# C-08_SODIMM.net
KiCad netlist of a schematic drawn in Altium Designer
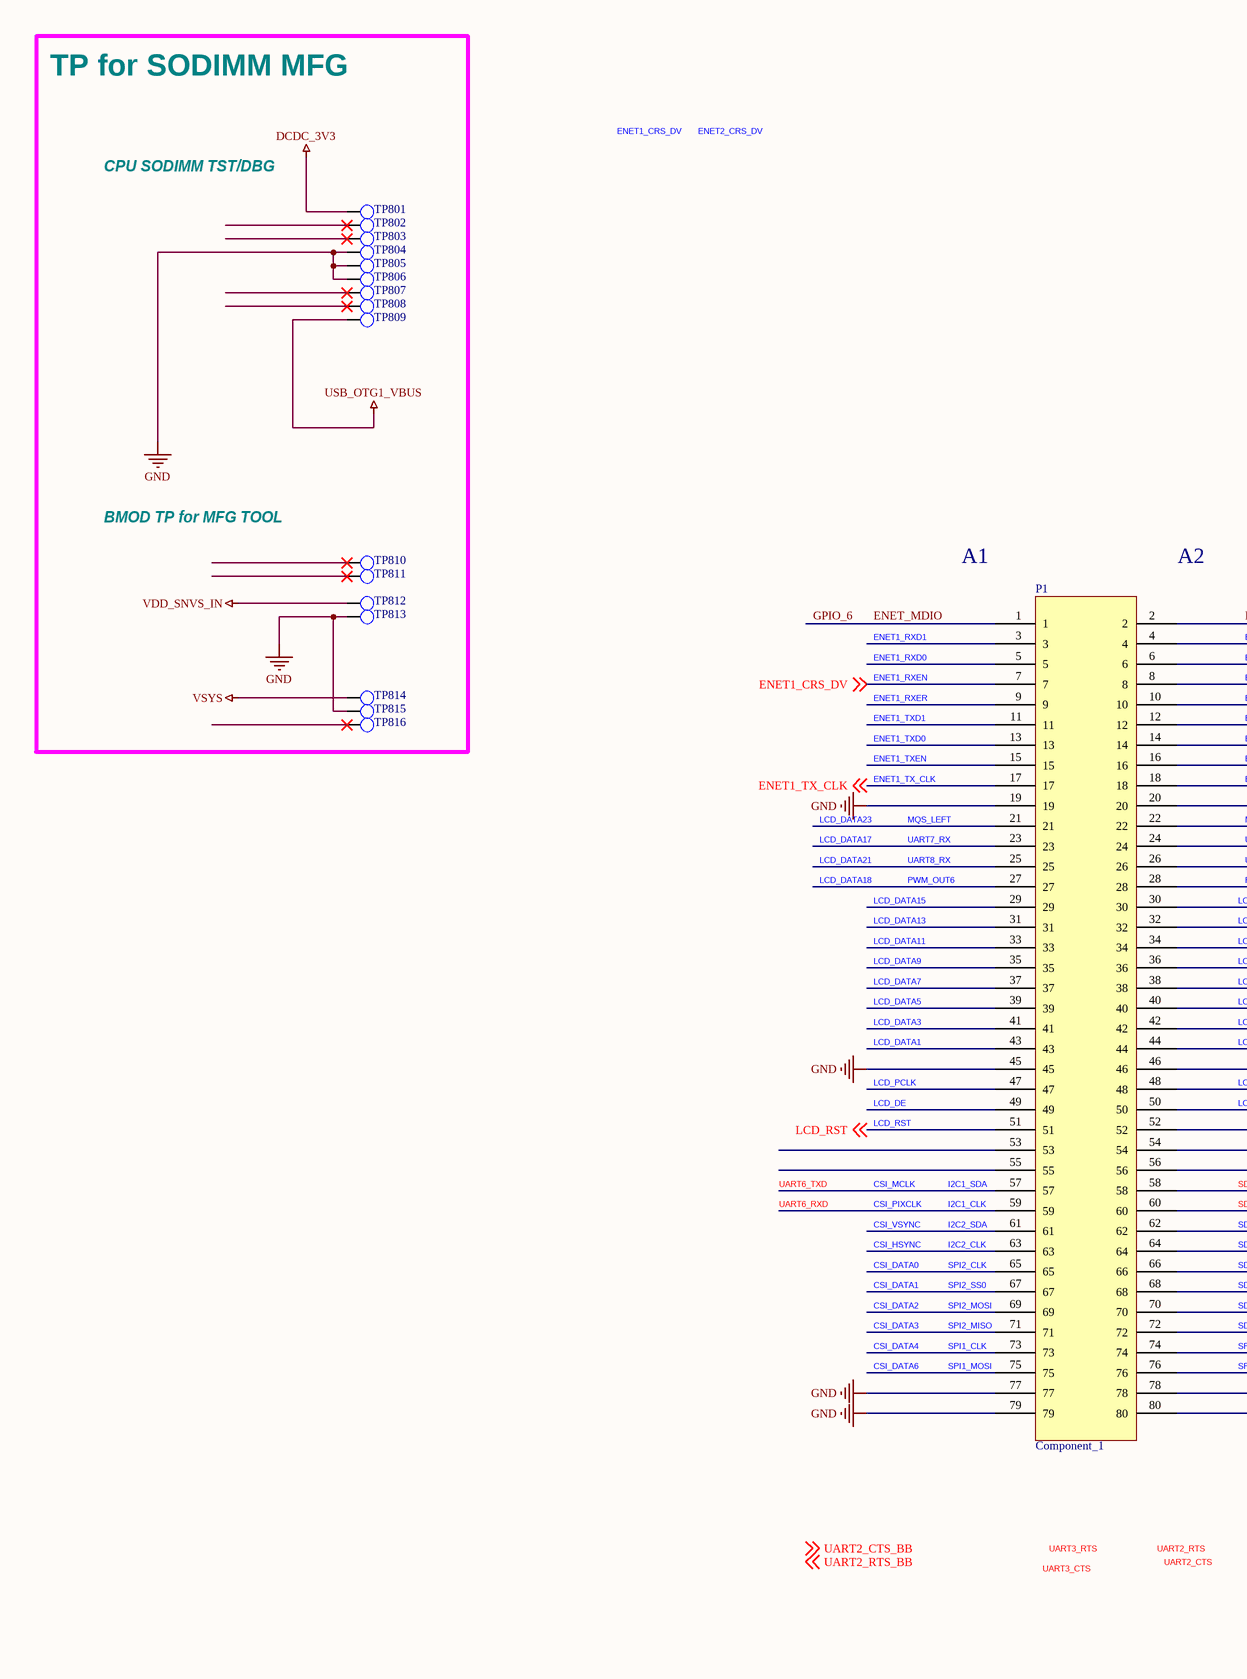
[diagram p0: C-08 SODIMM.SchDoc, left]
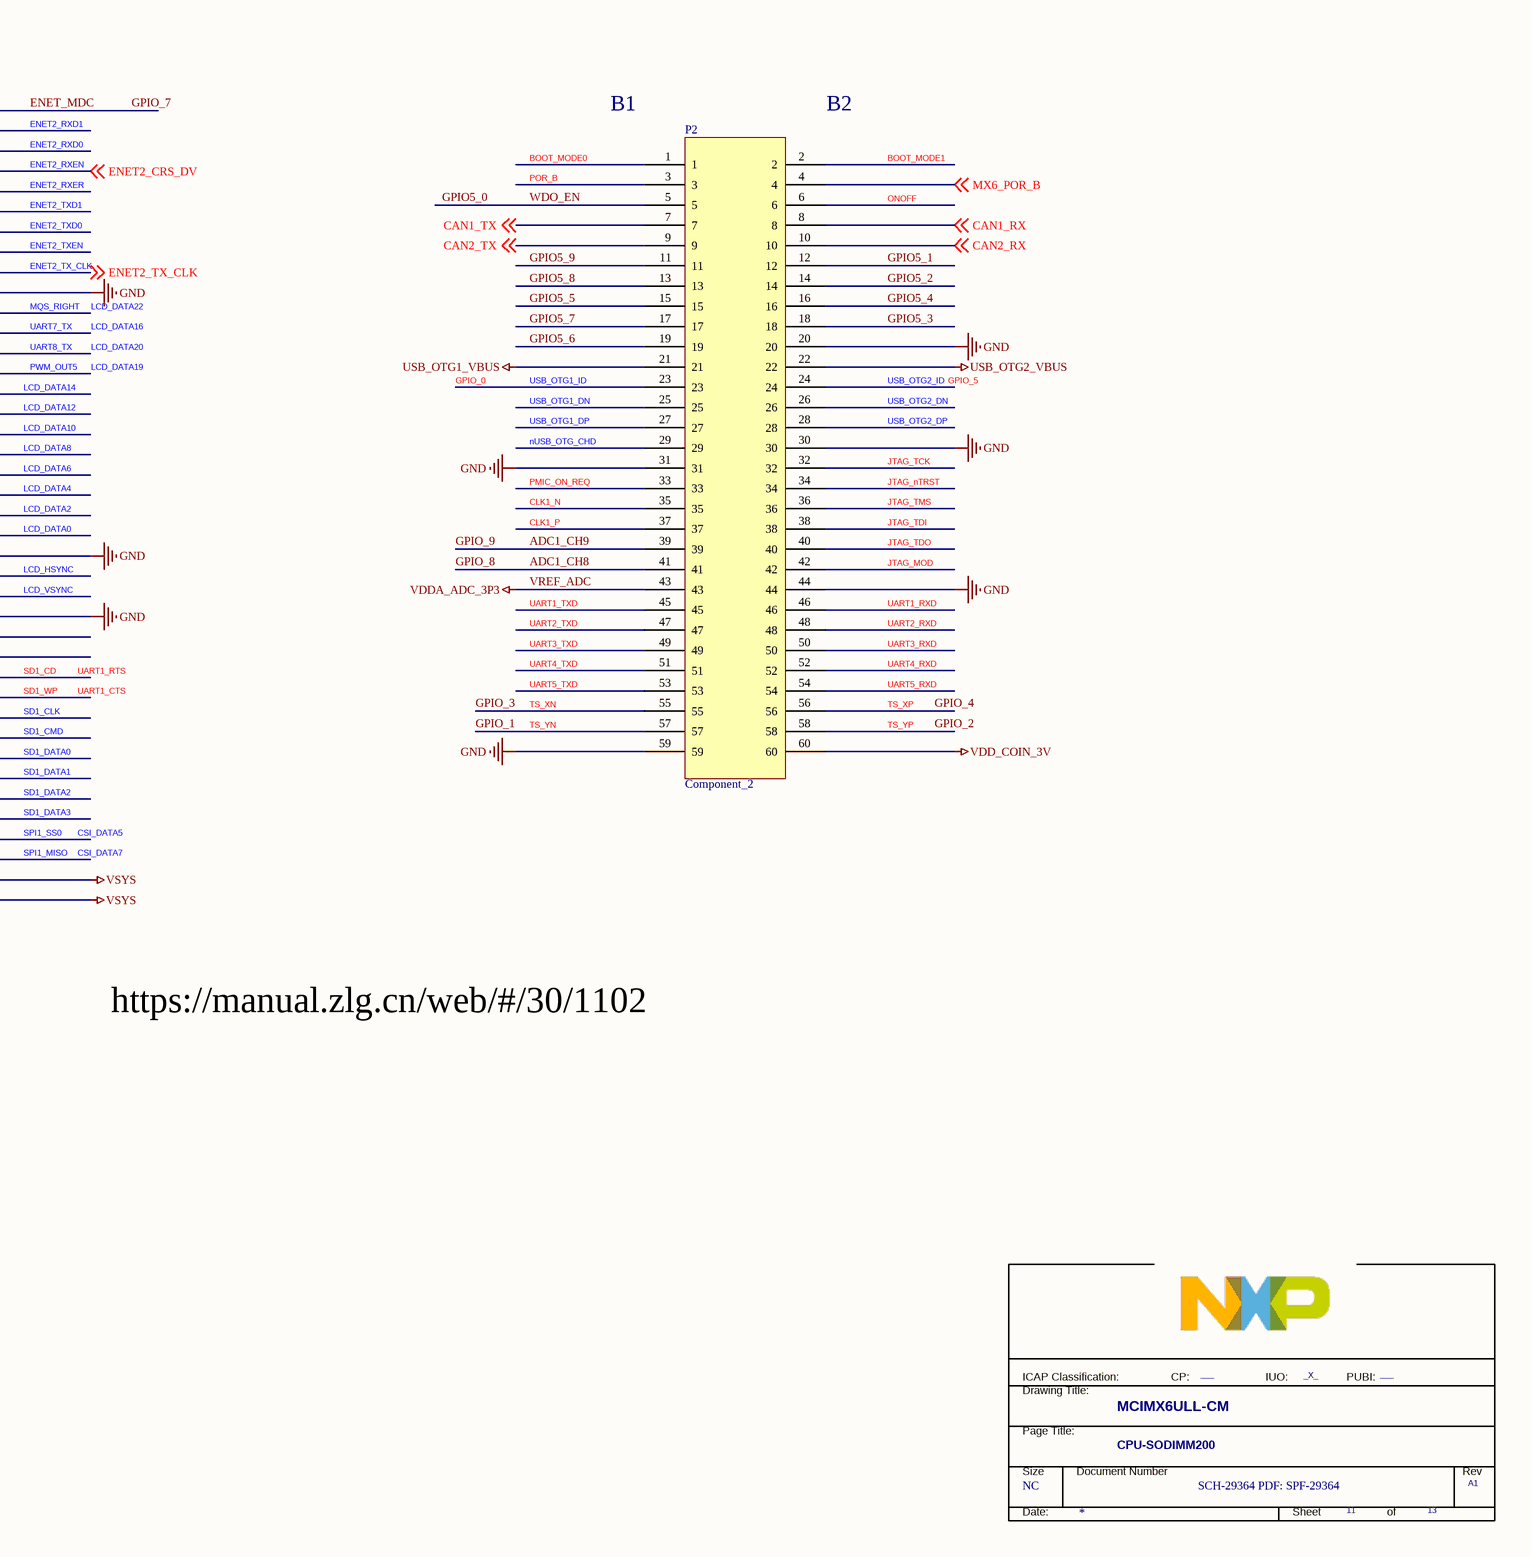
[diagram p1: C-08 SODIMM.SchDoc, right]

(export (version "E")
  (design (tool "Eeschema 10.0.6"))
  (components
    (comp (ref "*")
      (value "TitleBlock_FS")
      (fields
        (field (name "PAGETITLE") "CPU-SODIMM200")
        (field (name "PAGE COUNT") "13")
        (field (name "PAGE NUMBER") "11")
        (field (name "PAGE SIZE") "NC")
        (field (name "TITLE") "MCIMX6ULL-CM")
        (field (name "REVCODE") "A1")
        (field (name "DOC") "SCH-29364 PDF: SPF-29364")
        (field (name "FCP") "___")
        (field (name "PUBI") "___")
        (field (name "FIUO") "_X_")
      )
      (libsource (lib "*") (part "TitleBlock_FS"))
    )
    (comp (ref "P1")
      (value "Component_1")
      (footprint "CONN-SMD_80P-P0.50_HRS_DF12NB3.0-80DP-0.5V")
      (libsource (lib "Schlib1") (part "Component_1"))
    )
    (comp (ref "P2")
      (value "Component_2")
      (footprint "CONN-SMD_60P-P0.50_HRS_DF12NB3.0-60DS-0.5V-51")
      (libsource (lib "Schlib1") (part "Component_2"))
    )
    (comp (ref "TP801")
      (value "TP_35MIL")
      (footprint "testpoint_35mil")
      (description "TEST POINT PAD .035 SMT, no part to order")
      (libsource (lib "*") (part "T POINT R"))
    )
    (comp (ref "TP802")
      (value "TP_35MIL")
      (footprint "testpoint_35mil")
      (description "TEST POINT PAD .035 SMT, no part to order")
      (libsource (lib "*") (part "T POINT R"))
    )
    (comp (ref "TP803")
      (value "TP_35MIL")
      (footprint "testpoint_35mil")
      (description "TEST POINT PAD .035 SMT, no part to order")
      (libsource (lib "*") (part "T POINT R"))
    )
    (comp (ref "TP804")
      (value "TP_35MIL")
      (footprint "testpoint_35mil")
      (description "TEST POINT PAD .035 SMT, no part to order")
      (libsource (lib "*") (part "T POINT R"))
    )
    (comp (ref "TP805")
      (value "TP_35MIL")
      (footprint "testpoint_35mil")
      (description "TEST POINT PAD .035 SMT, no part to order")
      (libsource (lib "*") (part "T POINT R"))
    )
    (comp (ref "TP806")
      (value "TP_35MIL")
      (footprint "testpoint_35mil")
      (description "TEST POINT PAD .035 SMT, no part to order")
      (libsource (lib "*") (part "T POINT R"))
    )
    (comp (ref "TP807")
      (value "TP_35MIL")
      (footprint "testpoint_35mil")
      (description "TEST POINT PAD .035 SMT, no part to order")
      (libsource (lib "*") (part "T POINT R"))
    )
    (comp (ref "TP808")
      (value "TP_35MIL")
      (footprint "testpoint_35mil")
      (description "TEST POINT PAD .035 SMT, no part to order")
      (libsource (lib "*") (part "T POINT R"))
    )
    (comp (ref "TP809")
      (value "TP_35MIL")
      (footprint "testpoint_35mil")
      (description "TEST POINT PAD .035 SMT, no part to order")
      (libsource (lib "*") (part "T POINT R"))
    )
    (comp (ref "TP810")
      (value "TP_35MIL")
      (footprint "testpoint_35mil")
      (description "TEST POINT PAD .035 SMT, no part to order")
      (libsource (lib "*") (part "T POINT R"))
    )
    (comp (ref "TP811")
      (value "TP_35MIL")
      (footprint "testpoint_35mil")
      (description "TEST POINT PAD .035 SMT, no part to order")
      (libsource (lib "*") (part "T POINT R"))
    )
    (comp (ref "TP812")
      (value "TP_35MIL")
      (footprint "TPAD_015")
      (description "TEST POINT PAD .035 SMT, no part to order")
      (libsource (lib "*") (part "T POINT R"))
    )
    (comp (ref "TP813")
      (value "TP_35MIL")
      (footprint "testpoint_35mil")
      (description "TEST POINT PAD .035 SMT, no part to order")
      (libsource (lib "*") (part "T POINT R"))
    )
    (comp (ref "TP814")
      (value "TP_35MIL")
      (footprint "testpoint_35mil")
      (description "TEST POINT PAD .035 SMT, no part to order")
      (libsource (lib "*") (part "T POINT R"))
    )
    (comp (ref "TP815")
      (value "TP_35MIL")
      (footprint "testpoint_35mil")
      (description "TEST POINT PAD .035 SMT, no part to order")
      (libsource (lib "*") (part "T POINT R"))
    )
    (comp (ref "TP816")
      (value "TP_35MIL")
      (footprint "testpoint_35mil")
      (description "TEST POINT PAD .035 SMT, no part to order")
      (libsource (lib "*") (part "T POINT R"))
    )
  )
  (nets
    (net (code "1") (name "/ADC1_CH8") (class "Default")
      (node (ref "P2") (pin "41") (pinfunction "41_41") (pintype "passive"))
    )
    (net (code "2") (name "/ADC1_CH9") (class "Default")
      (node (ref "P2") (pin "39") (pinfunction "39_39") (pintype "passive"))
    )
    (net (code "3") (name "/BOOT_MODE0") (class "Default")
      (node (ref "P2") (pin "1") (pinfunction "1_1") (pintype "passive"))
    )
    (net (code "4") (name "/BOOT_MODE1") (class "Default")
      (node (ref "P2") (pin "2") (pinfunction "2_2") (pintype "passive"))
    )
    (net (code "5") (name "/CLK1_N") (class "Default")
      (node (ref "P2") (pin "35") (pinfunction "35_35") (pintype "passive"))
    )
    (net (code "6") (name "/CLK1_P") (class "Default")
      (node (ref "P2") (pin "37") (pinfunction "37_37") (pintype "passive"))
    )
    (net (code "7") (name "/CSI_DATA0") (class "Default")
      (node (ref "P1") (pin "65") (pinfunction "65_65") (pintype "passive"))
    )
    (net (code "8") (name "/CSI_DATA1") (class "Default")
      (node (ref "P1") (pin "67") (pinfunction "67_67") (pintype "passive"))
    )
    (net (code "9") (name "/CSI_DATA2") (class "Default")
      (node (ref "P1") (pin "69") (pinfunction "69_69") (pintype "passive"))
    )
    (net (code "10") (name "/CSI_DATA3") (class "Default")
      (node (ref "P1") (pin "71") (pinfunction "71_71") (pintype "passive"))
    )
    (net (code "11") (name "/CSI_DATA4") (class "Default")
      (node (ref "P1") (pin "73") (pinfunction "73_73") (pintype "passive"))
    )
    (net (code "12") (name "/CSI_DATA5") (class "Default")
      (node (ref "P1") (pin "74") (pinfunction "74_74") (pintype "passive"))
    )
    (net (code "13") (name "/CSI_DATA6") (class "Default")
      (node (ref "P1") (pin "75") (pinfunction "75_75") (pintype "passive"))
    )
    (net (code "14") (name "/CSI_DATA7") (class "Default")
      (node (ref "P1") (pin "76") (pinfunction "76_76") (pintype "passive"))
    )
    (net (code "15") (name "/CSI_HSYNC") (class "Default")
      (node (ref "P1") (pin "63") (pinfunction "63_63") (pintype "passive"))
    )
    (net (code "16") (name "/CSI_MCLK") (class "Default")
      (node (ref "P1") (pin "57") (pinfunction "57_57") (pintype "passive"))
    )
    (net (code "17") (name "/CSI_PIXCLK") (class "Default")
      (node (ref "P1") (pin "59") (pinfunction "59_59") (pintype "passive"))
    )
    (net (code "18") (name "/CSI_VSYNC") (class "Default")
      (node (ref "P1") (pin "61") (pinfunction "61_61") (pintype "passive"))
    )
    (net (code "19") (name "/ENET1_RXD0") (class "Default")
      (node (ref "P1") (pin "5") (pinfunction "5_5") (pintype "passive"))
    )
    (net (code "20") (name "/ENET1_RXD1") (class "Default")
      (node (ref "P1") (pin "3") (pinfunction "3_3") (pintype "passive"))
    )
    (net (code "21") (name "/ENET1_RXER") (class "Default")
      (node (ref "P1") (pin "9") (pinfunction "9_9") (pintype "passive"))
    )
    (net (code "22") (name "/ENET1_TXD0") (class "Default")
      (node (ref "P1") (pin "13") (pinfunction "13_13") (pintype "passive"))
    )
    (net (code "23") (name "/ENET1_TXD1") (class "Default")
      (node (ref "P1") (pin "11") (pinfunction "11_11") (pintype "passive"))
    )
    (net (code "24") (name "/ENET1_TXEN") (class "Default")
      (node (ref "P1") (pin "15") (pinfunction "15_15") (pintype "passive"))
    )
    (net (code "25") (name "/ENET2_RXD0") (class "Default")
      (node (ref "P1") (pin "6") (pinfunction "6_6") (pintype "passive"))
    )
    (net (code "26") (name "/ENET2_RXD1") (class "Default")
      (node (ref "P1") (pin "4") (pinfunction "4_4") (pintype "passive"))
    )
    (net (code "27") (name "/ENET2_RXER") (class "Default")
      (node (ref "P1") (pin "10") (pinfunction "10_10") (pintype "passive"))
    )
    (net (code "28") (name "/ENET2_TXD0") (class "Default")
      (node (ref "P1") (pin "14") (pinfunction "14_14") (pintype "passive"))
    )
    (net (code "29") (name "/ENET2_TXD1") (class "Default")
      (node (ref "P1") (pin "12") (pinfunction "12_12") (pintype "passive"))
    )
    (net (code "30") (name "/ENET2_TXEN") (class "Default")
      (node (ref "P1") (pin "16") (pinfunction "16_16") (pintype "passive"))
    )
    (net (code "31") (name "/ENET_MDC") (class "Default")
      (node (ref "P1") (pin "2") (pinfunction "2_2") (pintype "passive"))
    )
    (net (code "32") (name "/ENET_MDIO") (class "Default")
      (node (ref "P1") (pin "1") (pinfunction "1_1") (pintype "passive"))
    )
    (net (code "33") (name "/GPIO5_0") (class "Default")
      (node (ref "P2") (pin "5") (pinfunction "5_5") (pintype "passive"))
    )
    (net (code "34") (name "/GPIO5_1") (class "Default")
      (node (ref "P2") (pin "12") (pinfunction "12_12") (pintype "passive"))
    )
    (net (code "35") (name "/GPIO5_2") (class "Default")
      (node (ref "P2") (pin "14") (pinfunction "14_14") (pintype "passive"))
    )
    (net (code "36") (name "/GPIO5_3") (class "Default")
      (node (ref "P2") (pin "18") (pinfunction "18_18") (pintype "passive"))
    )
    (net (code "37") (name "/GPIO5_4") (class "Default")
      (node (ref "P2") (pin "16") (pinfunction "16_16") (pintype "passive"))
    )
    (net (code "38") (name "/GPIO5_5") (class "Default")
      (node (ref "P2") (pin "15") (pinfunction "15_15") (pintype "passive"))
    )
    (net (code "39") (name "/GPIO5_6") (class "Default")
      (node (ref "P2") (pin "19") (pinfunction "19_19") (pintype "passive"))
    )
    (net (code "40") (name "/GPIO5_7") (class "Default")
      (node (ref "P2") (pin "17") (pinfunction "17_17") (pintype "passive"))
    )
    (net (code "41") (name "/GPIO5_8") (class "Default")
      (node (ref "P2") (pin "13") (pinfunction "13_13") (pintype "passive"))
    )
    (net (code "42") (name "/GPIO5_9") (class "Default")
      (node (ref "P2") (pin "11") (pinfunction "11_11") (pintype "passive"))
    )
    (net (code "43") (name "/GPIO_0") (class "Default")
      (node (ref "P2") (pin "23") (pinfunction "23_23") (pintype "passive"))
    )
    (net (code "44") (name "/GPIO_1") (class "Default")
      (node (ref "P2") (pin "57") (pinfunction "57_57") (pintype "passive"))
    )
    (net (code "45") (name "/GPIO_2") (class "Default")
      (node (ref "P2") (pin "58") (pinfunction "58_58") (pintype "passive"))
    )
    (net (code "46") (name "/GPIO_3") (class "Default")
      (node (ref "P2") (pin "55") (pinfunction "55_55") (pintype "passive"))
    )
    (net (code "47") (name "/GPIO_4") (class "Default")
      (node (ref "P2") (pin "56") (pinfunction "56_56") (pintype "passive"))
    )
    (net (code "48") (name "/GPIO_5") (class "Default")
      (node (ref "P2") (pin "24") (pinfunction "24_24") (pintype "passive"))
    )
    (net (code "49") (name "/JTAG_MOD") (class "Default")
      (node (ref "P2") (pin "42") (pinfunction "42_42") (pintype "passive"))
    )
    (net (code "50") (name "/JTAG_TCK") (class "Default")
      (node (ref "P2") (pin "32") (pinfunction "32_32") (pintype "passive"))
    )
    (net (code "51") (name "/JTAG_TDI") (class "Default")
      (node (ref "P2") (pin "38") (pinfunction "38_38") (pintype "passive"))
    )
    (net (code "52") (name "/JTAG_TDO") (class "Default")
      (node (ref "P2") (pin "40") (pinfunction "40_40") (pintype "passive"))
    )
    (net (code "53") (name "/JTAG_TMS") (class "Default")
      (node (ref "P2") (pin "36") (pinfunction "36_36") (pintype "passive"))
    )
    (net (code "54") (name "/JTAG_nTRST") (class "Default")
      (node (ref "P2") (pin "34") (pinfunction "34_34") (pintype "passive"))
    )
    (net (code "55") (name "/LCD_DATA0") (class "Default")
      (node (ref "P1") (pin "44") (pinfunction "44_44") (pintype "passive"))
    )
    (net (code "56") (name "/LCD_DATA1") (class "Default")
      (node (ref "P1") (pin "43") (pinfunction "43_43") (pintype "passive"))
    )
    (net (code "57") (name "/LCD_DATA2") (class "Default")
      (node (ref "P1") (pin "42") (pinfunction "42_42") (pintype "passive"))
    )
    (net (code "58") (name "/LCD_DATA3") (class "Default")
      (node (ref "P1") (pin "41") (pinfunction "41_41") (pintype "passive"))
    )
    (net (code "59") (name "/LCD_DATA4") (class "Default")
      (node (ref "P1") (pin "40") (pinfunction "40_40") (pintype "passive"))
    )
    (net (code "60") (name "/LCD_DATA5") (class "Default")
      (node (ref "P1") (pin "39") (pinfunction "39_39") (pintype "passive"))
    )
    (net (code "61") (name "/LCD_DATA6") (class "Default")
      (node (ref "P1") (pin "38") (pinfunction "38_38") (pintype "passive"))
    )
    (net (code "62") (name "/LCD_DATA7") (class "Default")
      (node (ref "P1") (pin "37") (pinfunction "37_37") (pintype "passive"))
    )
    (net (code "63") (name "/LCD_DATA8") (class "Default")
      (node (ref "P1") (pin "36") (pinfunction "36_36") (pintype "passive"))
    )
    (net (code "64") (name "/LCD_DATA9") (class "Default")
      (node (ref "P1") (pin "35") (pinfunction "35_35") (pintype "passive"))
    )
    (net (code "65") (name "/LCD_DATA10") (class "Default")
      (node (ref "P1") (pin "34") (pinfunction "34_34") (pintype "passive"))
    )
    (net (code "66") (name "/LCD_DATA11") (class "Default")
      (node (ref "P1") (pin "33") (pinfunction "33_33") (pintype "passive"))
    )
    (net (code "67") (name "/LCD_DATA12") (class "Default")
      (node (ref "P1") (pin "32") (pinfunction "32_32") (pintype "passive"))
    )
    (net (code "68") (name "/LCD_DATA13") (class "Default")
      (node (ref "P1") (pin "31") (pinfunction "31_31") (pintype "passive"))
    )
    (net (code "69") (name "/LCD_DATA14") (class "Default")
      (node (ref "P1") (pin "30") (pinfunction "30_30") (pintype "passive"))
    )
    (net (code "70") (name "/LCD_DATA15") (class "Default")
      (node (ref "P1") (pin "29") (pinfunction "29_29") (pintype "passive"))
    )
    (net (code "71") (name "/LCD_DATA16") (class "Default")
      (node (ref "P1") (pin "24") (pinfunction "24_24") (pintype "passive"))
    )
    (net (code "72") (name "/LCD_DATA17") (class "Default")
      (node (ref "P1") (pin "23") (pinfunction "23_23") (pintype "passive"))
    )
    (net (code "73") (name "/LCD_DATA18") (class "Default")
      (node (ref "P1") (pin "27") (pinfunction "27_27") (pintype "passive"))
    )
    (net (code "74") (name "/LCD_DATA19") (class "Default")
      (node (ref "P1") (pin "28") (pinfunction "28_28") (pintype "passive"))
    )
    (net (code "75") (name "/LCD_DATA20") (class "Default")
      (node (ref "P1") (pin "26") (pinfunction "26_26") (pintype "passive"))
    )
    (net (code "76") (name "/LCD_DATA21") (class "Default")
      (node (ref "P1") (pin "25") (pinfunction "25_25") (pintype "passive"))
    )
    (net (code "77") (name "/LCD_DATA22") (class "Default")
      (node (ref "P1") (pin "22") (pinfunction "22_22") (pintype "passive"))
    )
    (net (code "78") (name "/LCD_DATA23") (class "Default")
      (node (ref "P1") (pin "21") (pinfunction "21_21") (pintype "passive"))
    )
    (net (code "79") (name "/LCD_DE") (class "Default")
      (node (ref "P1") (pin "49") (pinfunction "49_49") (pintype "passive"))
    )
    (net (code "80") (name "/LCD_HSYNC") (class "Default")
      (node (ref "P1") (pin "48") (pinfunction "48_48") (pintype "passive"))
    )
    (net (code "81") (name "/LCD_PCLK") (class "Default")
      (node (ref "P1") (pin "47") (pinfunction "47_47") (pintype "passive"))
    )
    (net (code "82") (name "/LCD_VSYNC") (class "Default")
      (node (ref "P1") (pin "50") (pinfunction "50_50") (pintype "passive"))
    )
    (net (code "83") (name "/ONOFF") (class "Default")
      (node (ref "P2") (pin "6") (pinfunction "6_6") (pintype "passive"))
    )
    (net (code "84") (name "/PMIC_ON_REQ") (class "Default")
      (node (ref "P2") (pin "33") (pinfunction "33_33") (pintype "passive"))
    )
    (net (code "85") (name "/POR_B") (class "Default")
      (node (ref "P2") (pin "3") (pinfunction "3_3") (pintype "passive"))
    )
    (net (code "86") (name "/SD1_CD") (class "Default")
      (node (ref "P1") (pin "58") (pinfunction "58_58") (pintype "passive"))
    )
    (net (code "87") (name "/SD1_CLK") (class "Default")
      (node (ref "P1") (pin "62") (pinfunction "62_62") (pintype "passive"))
    )
    (net (code "88") (name "/SD1_CMD") (class "Default")
      (node (ref "P1") (pin "64") (pinfunction "64_64") (pintype "passive"))
    )
    (net (code "89") (name "/SD1_DATA0") (class "Default")
      (node (ref "P1") (pin "66") (pinfunction "66_66") (pintype "passive"))
    )
    (net (code "90") (name "/SD1_DATA1") (class "Default")
      (node (ref "P1") (pin "68") (pinfunction "68_68") (pintype "passive"))
    )
    (net (code "91") (name "/SD1_DATA2") (class "Default")
      (node (ref "P1") (pin "70") (pinfunction "70_70") (pintype "passive"))
    )
    (net (code "92") (name "/SD1_DATA3") (class "Default")
      (node (ref "P1") (pin "72") (pinfunction "72_72") (pintype "passive"))
    )
    (net (code "93") (name "/SD1_WP") (class "Default")
      (node (ref "P1") (pin "60") (pinfunction "60_60") (pintype "passive"))
    )
    (net (code "94") (name "/UART1_RXD") (class "Default")
      (node (ref "P2") (pin "46") (pinfunction "46_46") (pintype "passive"))
    )
    (net (code "95") (name "/UART1_TXD") (class "Default")
      (node (ref "P2") (pin "45") (pinfunction "45_45") (pintype "passive"))
    )
    (net (code "98") (name "/UART2_RXD") (class "Default")
      (node (ref "P2") (pin "48") (pinfunction "48_48") (pintype "passive"))
    )
    (net (code "99") (name "/UART2_TXD") (class "Default")
      (node (ref "P2") (pin "47") (pinfunction "47_47") (pintype "passive"))
    )
    (net (code "102") (name "/UART3_RXD") (class "Default")
      (node (ref "P2") (pin "50") (pinfunction "50_50") (pintype "passive"))
    )
    (net (code "103") (name "/UART3_TXD") (class "Default")
      (node (ref "P2") (pin "49") (pinfunction "49_49") (pintype "passive"))
    )
    (net (code "104") (name "/UART4_RXD") (class "Default")
      (node (ref "P2") (pin "52") (pinfunction "52_52") (pintype "passive"))
    )
    (net (code "105") (name "/UART4_TXD") (class "Default")
      (node (ref "P2") (pin "51") (pinfunction "51_51") (pintype "passive"))
    )
    (net (code "106") (name "/UART5_RXD") (class "Default")
      (node (ref "P2") (pin "54") (pinfunction "54_54") (pintype "passive"))
    )
    (net (code "107") (name "/UART5_TXD") (class "Default")
      (node (ref "P2") (pin "53") (pinfunction "53_53") (pintype "passive"))
    )
    (net (code "108") (name "/USB_OTG1_DN") (class "Default")
      (node (ref "P2") (pin "25") (pinfunction "25_25") (pintype "passive"))
    )
    (net (code "109") (name "/USB_OTG1_DP") (class "Default")
      (node (ref "P2") (pin "27") (pinfunction "27_27") (pintype "passive"))
    )
    (net (code "110") (name "/USB_OTG2_DN") (class "Default")
      (node (ref "P2") (pin "26") (pinfunction "26_26") (pintype "passive"))
    )
    (net (code "111") (name "/USB_OTG2_DP") (class "Default")
      (node (ref "P2") (pin "28") (pinfunction "28_28") (pintype "passive"))
    )
    (net (code "112") (name "/nUSB_OTG_CHD") (class "Default")
      (node (ref "P2") (pin "29") (pinfunction "29_29") (pintype "passive"))
    )
    (net (code "113") (name "CAN1_RX") (class "Default")
      (node (ref "P2") (pin "8") (pinfunction "8_8") (pintype "passive"))
    )
    (net (code "114") (name "CAN1_TX") (class "Default")
      (node (ref "P2") (pin "7") (pinfunction "7_7") (pintype "passive"))
    )
    (net (code "115") (name "CAN2_RX") (class "Default")
      (node (ref "P2") (pin "10") (pinfunction "10_10") (pintype "passive"))
    )
    (net (code "116") (name "CAN2_TX") (class "Default")
      (node (ref "P2") (pin "9") (pinfunction "9_9") (pintype "passive"))
    )
    (net (code "117") (name "DCDC_3V3") (class "Default")
      (node (ref "TP801") (pin "1") (pinfunction "TP_1") (pintype "passive"))
    )
    (net (code "118") (name "ENET1_CRS_DV") (class "Default")
      (node (ref "P1") (pin "7") (pinfunction "7_7") (pintype "passive"))
    )
    (net (code "119") (name "ENET1_TX_CLK") (class "Default")
      (node (ref "P1") (pin "17") (pinfunction "17_17") (pintype "passive"))
    )
    (net (code "120") (name "ENET2_CRS_DV") (class "Default")
      (node (ref "P1") (pin "8") (pinfunction "8_8") (pintype "passive"))
    )
    (net (code "121") (name "ENET2_TX_CLK") (class "Default")
      (node (ref "P1") (pin "18") (pinfunction "18_18") (pintype "passive"))
    )
    (net (code "122") (name "GND") (class "Default")
      (node (ref "P1") (pin "19") (pinfunction "19_19") (pintype "passive"))
      (node (ref "P1") (pin "20") (pinfunction "20_20") (pintype "passive"))
      (node (ref "P1") (pin "45") (pinfunction "45_45") (pintype "passive"))
      (node (ref "P1") (pin "46") (pinfunction "46_46") (pintype "passive"))
      (node (ref "P1") (pin "52") (pinfunction "52_52") (pintype "passive"))
      (node (ref "P1") (pin "77") (pinfunction "77_77") (pintype "passive"))
      (node (ref "P1") (pin "79") (pinfunction "79_79") (pintype "passive"))
      (node (ref "P2") (pin "20") (pinfunction "20_20") (pintype "passive"))
      (node (ref "P2") (pin "30") (pinfunction "30_30") (pintype "passive"))
      (node (ref "P2") (pin "31") (pinfunction "31_31") (pintype "passive"))
      (node (ref "P2") (pin "44") (pinfunction "44_44") (pintype "passive"))
      (node (ref "P2") (pin "59") (pinfunction "59_59") (pintype "passive"))
      (node (ref "TP804") (pin "1") (pinfunction "TP_1") (pintype "passive"))
      (node (ref "TP805") (pin "1") (pinfunction "TP_1") (pintype "passive"))
      (node (ref "TP806") (pin "1") (pinfunction "TP_1") (pintype "passive"))
      (node (ref "TP813") (pin "1") (pinfunction "TP_1") (pintype "passive"))
      (node (ref "TP815") (pin "1") (pinfunction "TP_1") (pintype "passive"))
    )
    (net (code "123") (name "LCD_RST") (class "Default")
      (node (ref "P1") (pin "51") (pinfunction "51_51") (pintype "passive"))
    )
    (net (code "124") (name "MX6_POR_B") (class "Default")
      (node (ref "P2") (pin "4") (pinfunction "4_4") (pintype "passive"))
    )
    (net (code "127") (name "USB_OTG1_VBUS") (class "Default")
      (node (ref "P2") (pin "21") (pinfunction "21_21") (pintype "passive"))
      (node (ref "TP809") (pin "1") (pinfunction "TP_1") (pintype "passive"))
    )
    (net (code "128") (name "USB_OTG2_VBUS") (class "Default")
      (node (ref "P2") (pin "22") (pinfunction "22_22") (pintype "passive"))
    )
    (net (code "129") (name "VDDA_ADC_3P3") (class "Default")
      (node (ref "P2") (pin "43") (pinfunction "43_43") (pintype "passive"))
    )
    (net (code "130") (name "VDD_COIN_3V") (class "Default")
      (node (ref "P2") (pin "60") (pinfunction "60_60") (pintype "passive"))
    )
    (net (code "131") (name "VDD_SNVS_IN") (class "Default")
      (node (ref "TP812") (pin "1") (pinfunction "TP_1") (pintype "passive"))
    )
    (net (code "132") (name "VSYS") (class "Default")
      (node (ref "P1") (pin "78") (pinfunction "78_78") (pintype "passive"))
      (node (ref "P1") (pin "80") (pinfunction "80_80") (pintype "passive"))
      (node (ref "TP814") (pin "1") (pinfunction "TP_1") (pintype "passive"))
    )
    (net (code "133") (name "unconnected-(P1-Pad53)") (class "Default")
      (node (ref "P1") (pin "53") (pinfunction "53_53") (pintype "passive"))
    )
    (net (code "134") (name "unconnected-(P1-Pad54)") (class "Default")
      (node (ref "P1") (pin "54") (pinfunction "54_54") (pintype "passive"))
    )
    (net (code "135") (name "unconnected-(P1-Pad55)") (class "Default")
      (node (ref "P1") (pin "55") (pinfunction "55_55") (pintype "passive"))
    )
    (net (code "136") (name "unconnected-(P1-Pad56)") (class "Default")
      (node (ref "P1") (pin "56") (pinfunction "56_56") (pintype "passive"))
    )
    (net (code "137") (name "unconnected-(TP802-TP-Pad1)") (class "Default")
      (node (ref "TP802") (pin "1") (pinfunction "TP_1") (pintype "passive+no_connect"))
    )
    (net (code "138") (name "unconnected-(TP803-TP-Pad1)") (class "Default")
      (node (ref "TP803") (pin "1") (pinfunction "TP_1") (pintype "passive+no_connect"))
    )
    (net (code "139") (name "unconnected-(TP807-TP-Pad1)") (class "Default")
      (node (ref "TP807") (pin "1") (pinfunction "TP_1") (pintype "passive+no_connect"))
    )
    (net (code "140") (name "unconnected-(TP808-TP-Pad1)") (class "Default")
      (node (ref "TP808") (pin "1") (pinfunction "TP_1") (pintype "passive+no_connect"))
    )
    (net (code "141") (name "unconnected-(TP810-TP-Pad1)") (class "Default")
      (node (ref "TP810") (pin "1") (pinfunction "TP_1") (pintype "passive+no_connect"))
    )
    (net (code "142") (name "unconnected-(TP811-TP-Pad1)") (class "Default")
      (node (ref "TP811") (pin "1") (pinfunction "TP_1") (pintype "passive+no_connect"))
    )
    (net (code "143") (name "unconnected-(TP816-TP-Pad1)") (class "Default")
      (node (ref "TP816") (pin "1") (pinfunction "TP_1") (pintype "passive+no_connect"))
    )
  )
)
